# 11_CONNECTOR.net
KiCad netlist of a schematic drawn in Altium Designer
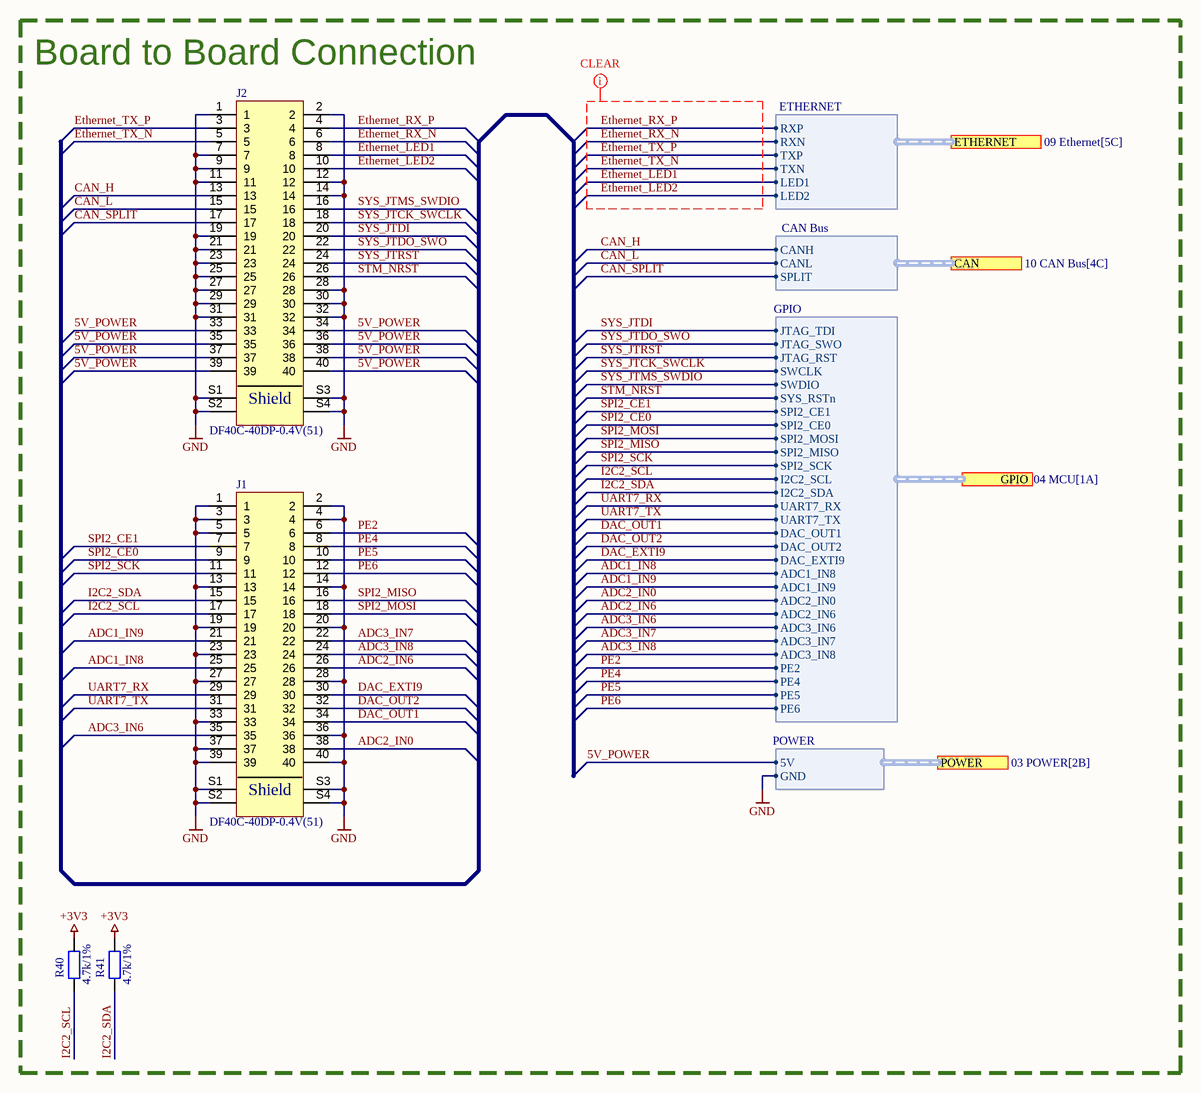
[diagram p0: 11 CONNECTOR.SchDoc]

(export (version "E")
  (design (tool "Eeschema 10.0.6"))
  (components
    (comp (ref "J1")
      (value "DF40C-40DP-0.4V(51)")
      (footprint "DF40C-40DP-0.4V(51)")
      (description "40 Position Connector Plug, Outer Shroud Contacts Surface Mount Gold")
      (libsource (lib "Symbol") (part "DF40C-40DP-0.4V(51)"))
    )
    (comp (ref "J2")
      (value "DF40C-40DP-0.4V(51)")
      (footprint "DF40C-40DP-0.4V(51)")
      (description "40 Position Connector Plug, Outer Shroud Contacts Surface Mount Gold")
      (libsource (lib "Symbol") (part "DF40C-40DP-0.4V(51)"))
    )
    (comp (ref "R40")
      (value "4.7k/1%")
      (footprint "RESC1005X04M-0402")
      (description "4.7 kOhms ±1% 0.063W, 1/16W Chip Resistor 0402 (1005 Metric) Moisture Resistant Thick Film")
      (fields (field (name "MPN") "RC0402FR-074K7L"))
      (libsource (lib "Symbol") (part "RC0402FR-074K7L"))
    )
    (comp (ref "R41")
      (value "4.7k/1%")
      (footprint "RESC1005X04M-0402")
      (description "4.7 kOhms ±1% 0.063W, 1/16W Chip Resistor 0402 (1005 Metric) Moisture Resistant Thick Film")
      (fields (field (name "MPN") "RC0402FR-074K7L"))
      (libsource (lib "Symbol") (part "RC0402FR-074K7L"))
    )
  )
  (nets
    (net (code "6") (name "+3V3") (class "Default")
      (node (ref "R40") (pin "2") (pinfunction "2_2") (pintype "passive"))
      (node (ref "R41") (pin "2") (pinfunction "2_2") (pintype "passive"))
    )
    (net (code "7") (name "/5V_POWER") (class "Default")
      (node (ref "J2") (pin "33") (pinfunction "33_33") (pintype "passive"))
      (node (ref "J2") (pin "34") (pinfunction "34_34") (pintype "passive"))
      (node (ref "J2") (pin "35") (pinfunction "35_35") (pintype "passive"))
      (node (ref "J2") (pin "36") (pinfunction "36_36") (pintype "passive"))
      (node (ref "J2") (pin "37") (pinfunction "37_37") (pintype "passive"))
      (node (ref "J2") (pin "38") (pinfunction "38_38") (pintype "passive"))
      (node (ref "J2") (pin "39") (pinfunction "39_39") (pintype "passive"))
      (node (ref "J2") (pin "40") (pinfunction "40_40") (pintype "passive"))
    )
    (net (code "8") (name "/ADC1_IN8") (class "Default")
      (node (ref "J1") (pin "25") (pinfunction "25_25") (pintype "passive"))
    )
    (net (code "9") (name "/ADC1_IN9") (class "Default")
      (node (ref "J1") (pin "21") (pinfunction "21_21") (pintype "passive"))
    )
    (net (code "10") (name "/ADC2_IN0") (class "Default")
      (node (ref "J1") (pin "38") (pinfunction "38_38") (pintype "passive"))
    )
    (net (code "11") (name "/ADC2_IN6") (class "Default")
      (node (ref "J1") (pin "26") (pinfunction "26_26") (pintype "passive"))
    )
    (net (code "12") (name "/ADC3_IN6") (class "Default")
      (node (ref "J1") (pin "35") (pinfunction "35_35") (pintype "passive"))
    )
    (net (code "13") (name "/ADC3_IN7") (class "Default")
      (node (ref "J1") (pin "22") (pinfunction "22_22") (pintype "passive"))
    )
    (net (code "14") (name "/ADC3_IN8") (class "Default")
      (node (ref "J1") (pin "24") (pinfunction "24_24") (pintype "passive"))
    )
    (net (code "15") (name "/CAN_H") (class "Default")
      (node (ref "J2") (pin "13") (pinfunction "13_13") (pintype "passive"))
    )
    (net (code "16") (name "/CAN_L") (class "Default")
      (node (ref "J2") (pin "15") (pinfunction "15_15") (pintype "passive"))
    )
    (net (code "17") (name "/CAN_SPLIT") (class "Default")
      (node (ref "J2") (pin "17") (pinfunction "17_17") (pintype "passive"))
    )
    (net (code "18") (name "/DAC_EXTI9") (class "Default")
      (node (ref "J1") (pin "30") (pinfunction "30_30") (pintype "passive"))
    )
    (net (code "19") (name "/DAC_OUT1") (class "Default")
      (node (ref "J1") (pin "34") (pinfunction "34_34") (pintype "passive"))
    )
    (net (code "20") (name "/DAC_OUT2") (class "Default")
      (node (ref "J1") (pin "32") (pinfunction "32_32") (pintype "passive"))
    )
    (net (code "21") (name "/Ethernet_LED1") (class "Default")
      (node (ref "J2") (pin "8") (pinfunction "8_8") (pintype "passive"))
    )
    (net (code "22") (name "/Ethernet_LED2") (class "Default")
      (node (ref "J2") (pin "10") (pinfunction "10_10") (pintype "passive"))
    )
    (net (code "23") (name "/Ethernet_RX_N") (class "Default")
      (node (ref "J2") (pin "6") (pinfunction "6_6") (pintype "passive"))
    )
    (net (code "24") (name "/Ethernet_RX_P") (class "Default")
      (node (ref "J2") (pin "4") (pinfunction "4_4") (pintype "passive"))
    )
    (net (code "25") (name "/Ethernet_TX_N") (class "Default")
      (node (ref "J2") (pin "5") (pinfunction "5_5") (pintype "passive"))
    )
    (net (code "26") (name "/Ethernet_TX_P") (class "Default")
      (node (ref "J2") (pin "3") (pinfunction "3_3") (pintype "passive"))
    )
    (net (code "27") (name "/I2C2_SCL") (class "Default")
      (node (ref "J1") (pin "17") (pinfunction "17_17") (pintype "passive"))
      (node (ref "R40") (pin "1") (pinfunction "1_1") (pintype "passive"))
    )
    (net (code "28") (name "/I2C2_SDA") (class "Default")
      (node (ref "J1") (pin "15") (pinfunction "15_15") (pintype "passive"))
      (node (ref "R41") (pin "1") (pinfunction "1_1") (pintype "passive"))
    )
    (net (code "29") (name "/PE2") (class "Default")
      (node (ref "J1") (pin "6") (pinfunction "6_6") (pintype "passive"))
    )
    (net (code "30") (name "/PE4") (class "Default")
      (node (ref "J1") (pin "8") (pinfunction "8_8") (pintype "passive"))
    )
    (net (code "31") (name "/PE5") (class "Default")
      (node (ref "J1") (pin "10") (pinfunction "10_10") (pintype "passive"))
    )
    (net (code "32") (name "/PE6") (class "Default")
      (node (ref "J1") (pin "12") (pinfunction "12_12") (pintype "passive"))
    )
    (net (code "33") (name "/SPI2_CE0") (class "Default")
      (node (ref "J1") (pin "9") (pinfunction "9_9") (pintype "passive"))
    )
    (net (code "34") (name "/SPI2_CE1") (class "Default")
      (node (ref "J1") (pin "7") (pinfunction "7_7") (pintype "passive"))
    )
    (net (code "35") (name "/SPI2_MISO") (class "Default")
      (node (ref "J1") (pin "16") (pinfunction "16_16") (pintype "passive"))
    )
    (net (code "36") (name "/SPI2_MOSI") (class "Default")
      (node (ref "J1") (pin "18") (pinfunction "18_18") (pintype "passive"))
    )
    (net (code "37") (name "/SPI2_SCK") (class "Default")
      (node (ref "J1") (pin "11") (pinfunction "11_11") (pintype "passive"))
    )
    (net (code "38") (name "/STM_NRST") (class "Default")
      (node (ref "J2") (pin "26") (pinfunction "26_26") (pintype "passive"))
    )
    (net (code "39") (name "/SYS_JTCK_SWCLK") (class "Default")
      (node (ref "J2") (pin "18") (pinfunction "18_18") (pintype "passive"))
    )
    (net (code "40") (name "/SYS_JTDI") (class "Default")
      (node (ref "J2") (pin "20") (pinfunction "20_20") (pintype "passive"))
    )
    (net (code "41") (name "/SYS_JTDO_SWO") (class "Default")
      (node (ref "J2") (pin "22") (pinfunction "22_22") (pintype "passive"))
    )
    (net (code "42") (name "/SYS_JTMS_SWDIO") (class "Default")
      (node (ref "J2") (pin "16") (pinfunction "16_16") (pintype "passive"))
    )
    (net (code "43") (name "/SYS_JTRST") (class "Default")
      (node (ref "J2") (pin "24") (pinfunction "24_24") (pintype "passive"))
    )
    (net (code "44") (name "/UART7_RX") (class "Default")
      (node (ref "J1") (pin "29") (pinfunction "29_29") (pintype "passive"))
    )
    (net (code "45") (name "/UART7_TX") (class "Default")
      (node (ref "J1") (pin "31") (pinfunction "31_31") (pintype "passive"))
    )
    (net (code "50") (name "GND") (class "Default")
      (node (ref "J1") (pin "1") (pinfunction "1_1") (pintype "passive"))
      (node (ref "J1") (pin "13") (pinfunction "13_13") (pintype "passive"))
      (node (ref "J1") (pin "14") (pinfunction "14_14") (pintype "passive"))
      (node (ref "J1") (pin "19") (pinfunction "19_19") (pintype "passive"))
      (node (ref "J1") (pin "2") (pinfunction "2_2") (pintype "passive"))
      (node (ref "J1") (pin "20") (pinfunction "20_20") (pintype "passive"))
      (node (ref "J1") (pin "23") (pinfunction "23_23") (pintype "passive"))
      (node (ref "J1") (pin "27") (pinfunction "27_27") (pintype "passive"))
      (node (ref "J1") (pin "28") (pinfunction "28_28") (pintype "passive"))
      (node (ref "J1") (pin "3") (pinfunction "3_3") (pintype "passive"))
      (node (ref "J1") (pin "33") (pinfunction "33_33") (pintype "passive"))
      (node (ref "J1") (pin "36") (pinfunction "36_36") (pintype "passive"))
      (node (ref "J1") (pin "37") (pinfunction "37_37") (pintype "passive"))
      (node (ref "J1") (pin "39") (pinfunction "39_39") (pintype "passive"))
      (node (ref "J1") (pin "4") (pinfunction "4_4") (pintype "passive"))
      (node (ref "J1") (pin "40") (pinfunction "40_40") (pintype "passive"))
      (node (ref "J1") (pin "5") (pinfunction "5_5") (pintype "passive"))
      (node (ref "J1") (pin "S1") (pintype "passive"))
      (node (ref "J1") (pin "S2") (pintype "passive"))
      (node (ref "J1") (pin "S3") (pintype "passive"))
      (node (ref "J1") (pin "S4") (pintype "passive"))
      (node (ref "J2") (pin "1") (pinfunction "1_1") (pintype "passive"))
      (node (ref "J2") (pin "11") (pinfunction "11_11") (pintype "passive"))
      (node (ref "J2") (pin "12") (pinfunction "12_12") (pintype "passive"))
      (node (ref "J2") (pin "14") (pinfunction "14_14") (pintype "passive"))
      (node (ref "J2") (pin "19") (pinfunction "19_19") (pintype "passive"))
      (node (ref "J2") (pin "2") (pinfunction "2_2") (pintype "passive"))
      (node (ref "J2") (pin "21") (pinfunction "21_21") (pintype "passive"))
      (node (ref "J2") (pin "23") (pinfunction "23_23") (pintype "passive"))
      (node (ref "J2") (pin "25") (pinfunction "25_25") (pintype "passive"))
      (node (ref "J2") (pin "27") (pinfunction "27_27") (pintype "passive"))
      (node (ref "J2") (pin "28") (pinfunction "28_28") (pintype "passive"))
      (node (ref "J2") (pin "29") (pinfunction "29_29") (pintype "passive"))
      (node (ref "J2") (pin "30") (pinfunction "30_30") (pintype "passive"))
      (node (ref "J2") (pin "31") (pinfunction "31_31") (pintype "passive"))
      (node (ref "J2") (pin "32") (pinfunction "32_32") (pintype "passive"))
      (node (ref "J2") (pin "7") (pinfunction "7_7") (pintype "passive"))
      (node (ref "J2") (pin "9") (pinfunction "9_9") (pintype "passive"))
      (node (ref "J2") (pin "S1") (pintype "passive"))
      (node (ref "J2") (pin "S2") (pintype "passive"))
      (node (ref "J2") (pin "S3") (pintype "passive"))
      (node (ref "J2") (pin "S4") (pintype "passive"))
    )
  )
)
